# pcie-led.net
KiCad netlist of a schematic drawn in EAGLE
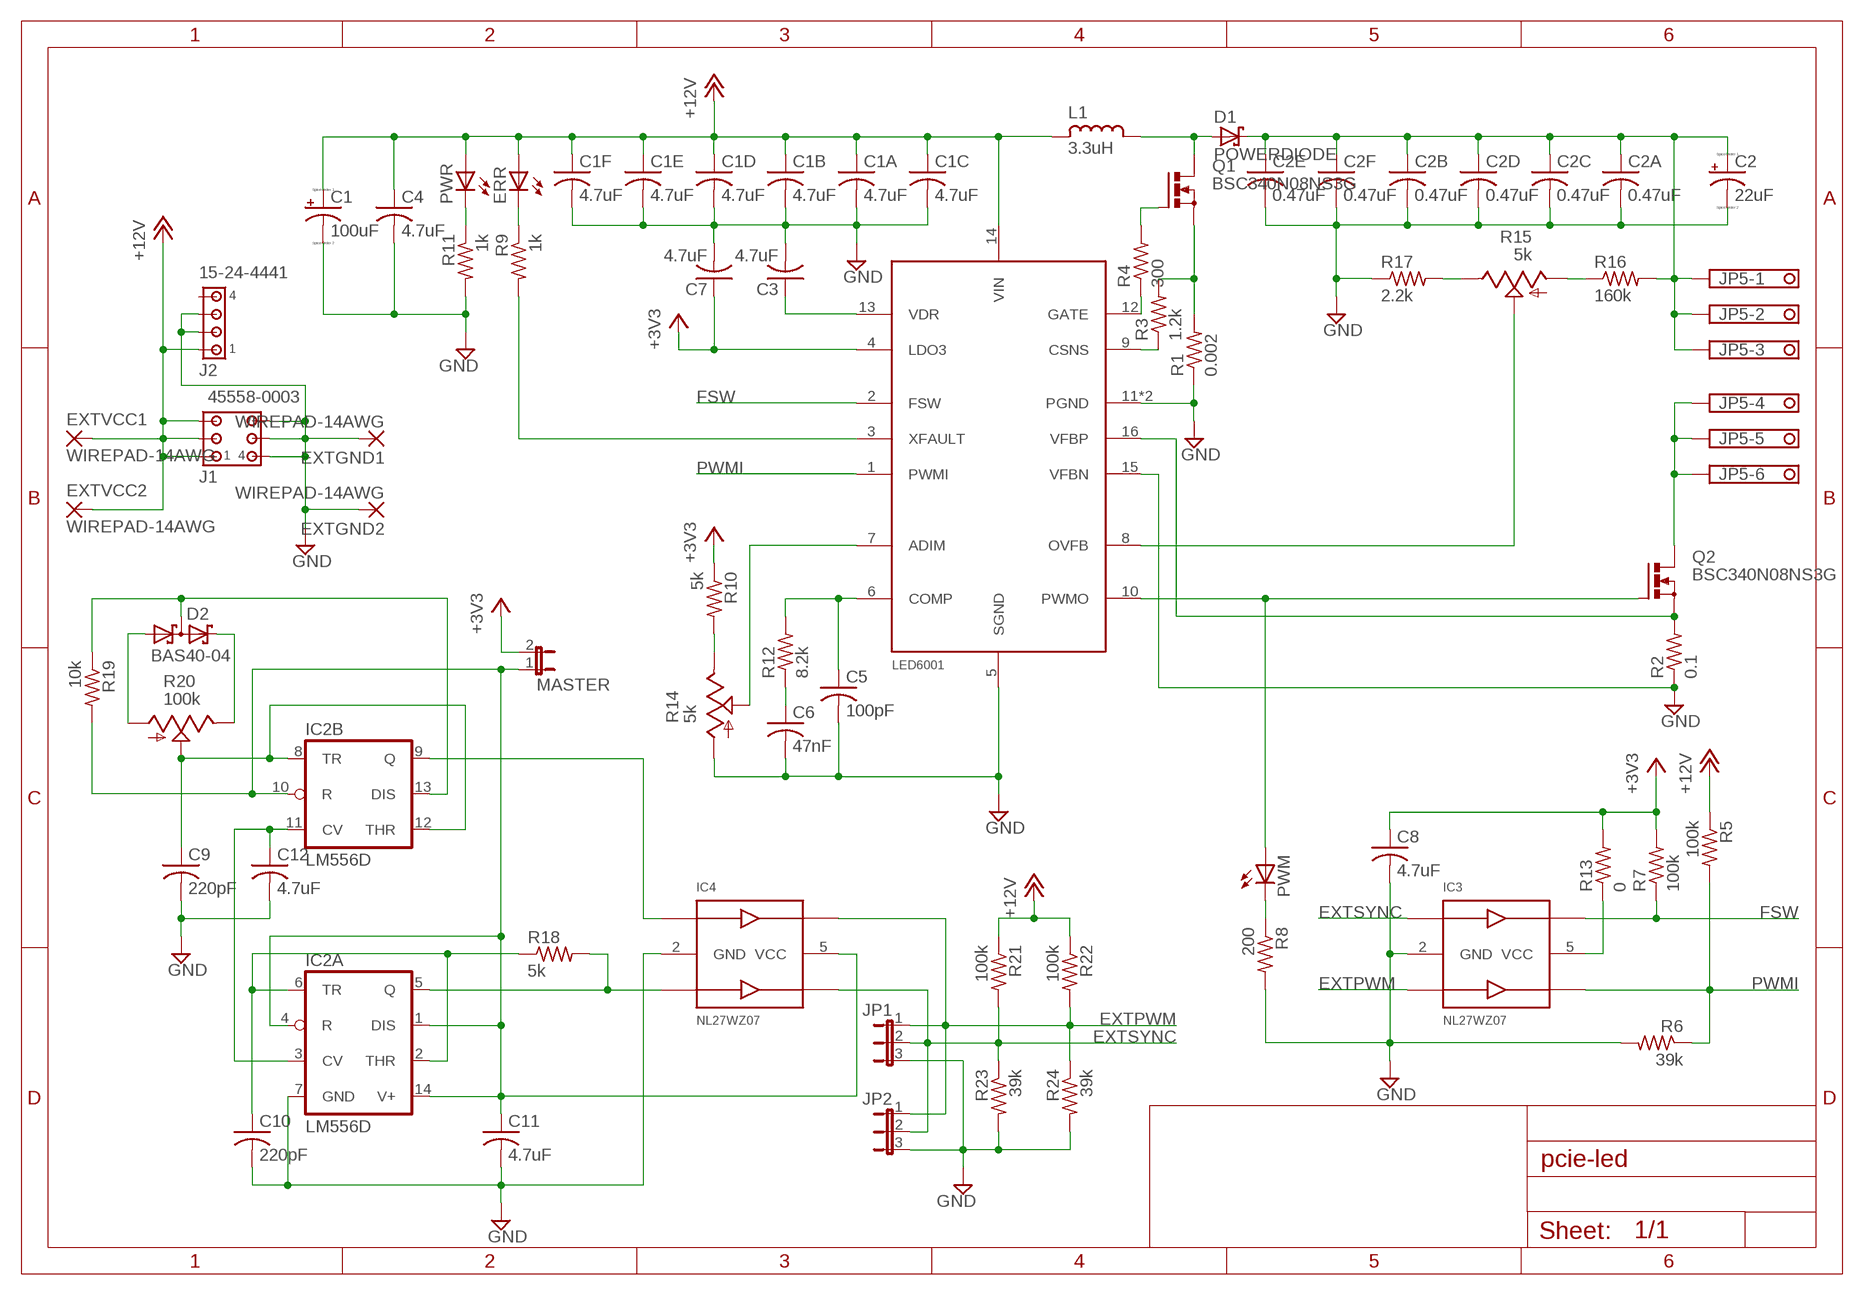
[diagram p0: schematic, sheet 1]

(export (version "E")
  (design (tool "Eeschema 10.0.6"))
  (components
    (comp (ref "C1")
      (value "100uF")
      (footprint "eagle-import:E3,5-8")
      (libsource (lib "eagle-import") (part "CPOL-USE3.5-8"))
    )
    (comp (ref "C1A")
      (value "4.7uF")
      (footprint "eagle-import:C0805")
      (libsource (lib "eagle-import") (part "C-USC0805"))
    )
    (comp (ref "C1B")
      (value "4.7uF")
      (footprint "eagle-import:C0805")
      (libsource (lib "eagle-import") (part "C-USC0805"))
    )
    (comp (ref "C1C")
      (value "4.7uF")
      (footprint "eagle-import:C0805")
      (libsource (lib "eagle-import") (part "C-USC0805"))
    )
    (comp (ref "C1D")
      (value "4.7uF")
      (footprint "eagle-import:C0805")
      (libsource (lib "eagle-import") (part "C-USC0805"))
    )
    (comp (ref "C1E")
      (value "4.7uF")
      (footprint "eagle-import:C0805")
      (libsource (lib "eagle-import") (part "C-USC0805"))
    )
    (comp (ref "C1F")
      (value "4.7uF")
      (footprint "eagle-import:C0805")
      (libsource (lib "eagle-import") (part "C-USC0805"))
    )
    (comp (ref "C2")
      (value "22uF")
      (footprint "eagle-import:E3,5-8")
      (libsource (lib "eagle-import") (part "CPOL-USE3.5-8"))
    )
    (comp (ref "C2A")
      (value "0.47uF")
      (footprint "eagle-import:C0805")
      (libsource (lib "eagle-import") (part "C-USC0805"))
    )
    (comp (ref "C2B")
      (value "0.47uF")
      (footprint "eagle-import:C0805")
      (libsource (lib "eagle-import") (part "C-USC0805"))
    )
    (comp (ref "C2C")
      (value "0.47uF")
      (footprint "eagle-import:C0805")
      (libsource (lib "eagle-import") (part "C-USC0805"))
    )
    (comp (ref "C2D")
      (value "0.47uF")
      (footprint "eagle-import:C0805")
      (libsource (lib "eagle-import") (part "C-USC0805"))
    )
    (comp (ref "C2E")
      (value "0.47uF")
      (footprint "eagle-import:C0805")
      (libsource (lib "eagle-import") (part "C-USC0805"))
    )
    (comp (ref "C2F")
      (value "0.47uF")
      (footprint "eagle-import:C0805")
      (libsource (lib "eagle-import") (part "C-USC0805"))
    )
    (comp (ref "C3")
      (value "4.7uF")
      (footprint "eagle-import:C0603")
      (libsource (lib "eagle-import") (part "C-USC0603"))
    )
    (comp (ref "C4")
      (value "4.7uF")
      (footprint "eagle-import:C0603")
      (libsource (lib "eagle-import") (part "C-USC0603"))
    )
    (comp (ref "C5")
      (value "100pF")
      (footprint "eagle-import:C0603")
      (libsource (lib "eagle-import") (part "C-USC0603"))
    )
    (comp (ref "C6")
      (value "47nF")
      (footprint "eagle-import:C0603")
      (libsource (lib "eagle-import") (part "C-USC0603"))
    )
    (comp (ref "C7")
      (value "4.7uF")
      (footprint "eagle-import:C0603")
      (libsource (lib "eagle-import") (part "C-USC0603"))
    )
    (comp (ref "C8")
      (value "4.7uF")
      (footprint "eagle-import:C0603")
      (libsource (lib "eagle-import") (part "C-USC0603"))
    )
    (comp (ref "C9")
      (value "220pF")
      (footprint "eagle-import:C0603")
      (libsource (lib "eagle-import") (part "C-USC0603"))
    )
    (comp (ref "C10")
      (value "220pF")
      (footprint "eagle-import:C0603")
      (libsource (lib "eagle-import") (part "C-USC0603"))
    )
    (comp (ref "C11")
      (value "4.7uF")
      (footprint "eagle-import:C0603")
      (libsource (lib "eagle-import") (part "C-USC0603"))
    )
    (comp (ref "C12")
      (value "4.7uF")
      (footprint "eagle-import:C0603")
      (libsource (lib "eagle-import") (part "C-USC0603"))
    )
    (comp (ref "D1")
      (value "POWERDIODE")
      (footprint "eagle-import:LFPACK56-TO277")
      (libsource (lib "eagle-import") (part "POWERDIODE"))
    )
    (comp (ref "D2")
      (value "BAS40-04")
      (footprint "eagle-import:SOT23")
      (libsource (lib "eagle-import") (part "BAS40-04"))
    )
    (comp (ref "ERR")
      (value "LEDCHIP-LED0805")
      (footprint "eagle-import:CHIP-LED0805")
      (libsource (lib "eagle-import") (part "LEDCHIP-LED0805"))
    )
    (comp (ref "EXTGND1")
      (value "WIREPAD-14AWG")
      (footprint "eagle-import:WIREPAD-14AWG")
      (libsource (lib "eagle-import") (part "WIREPAD-14AWG"))
    )
    (comp (ref "EXTGND2")
      (value "WIREPAD-14AWG")
      (footprint "eagle-import:WIREPAD-14AWG")
      (libsource (lib "eagle-import") (part "WIREPAD-14AWG"))
    )
    (comp (ref "EXTVCC1")
      (value "WIREPAD-14AWG")
      (footprint "eagle-import:WIREPAD-14AWG")
      (libsource (lib "eagle-import") (part "WIREPAD-14AWG"))
    )
    (comp (ref "EXTVCC2")
      (value "WIREPAD-14AWG")
      (footprint "eagle-import:WIREPAD-14AWG")
      (libsource (lib "eagle-import") (part "WIREPAD-14AWG"))
    )
    (comp (ref "IC1")
      (value "LED6001")
      (footprint "eagle-import:HTSSOP-16")
      (libsource (lib "eagle-import") (part "LED6001"))
    )
    (comp (ref "IC2")
      (value "LM556D")
      (footprint "eagle-import:SO14")
      (libsource (lib "eagle-import") (part "556DLM"))
    )
    (comp (ref "IC3")
      (value "NL27WZ07")
      (footprint "eagle-import:SOT363")
      (libsource (lib "eagle-import") (part "NL27WZ07"))
    )
    (comp (ref "IC4")
      (value "NL27WZ07")
      (footprint "eagle-import:SOT363")
      (libsource (lib "eagle-import") (part "NL27WZ07"))
    )
    (comp (ref "J1")
      (value "45558-0003")
      (footprint "eagle-import:45558-0003")
      (libsource (lib "eagle-import") (part "45558-0003"))
    )
    (comp (ref "J2")
      (value "15-24-4441")
      (footprint "eagle-import:15-24-4441")
      (libsource (lib "eagle-import") (part "15-24-4441"))
    )
    (comp (ref "JP1")
      (value "JP2E")
      (footprint "eagle-import:JP2")
      (libsource (lib "eagle-import") (part "JP2E"))
    )
    (comp (ref "JP2")
      (value "JP2E")
      (footprint "eagle-import:JP2")
      (libsource (lib "eagle-import") (part "JP2E"))
    )
    (comp (ref "JP5")
      (value "OSTTE06")
      (footprint "eagle-import:OSTTE06")
      (libsource (lib "eagle-import") (part "OSTTE06"))
    )
    (comp (ref "L1")
      (value "3.3uH")
      (footprint "eagle-import:SRP1770TA")
      (libsource (lib "eagle-import") (part "SRP1770TA"))
    )
    (comp (ref "MASTER")
      (value "JP1E")
      (footprint "eagle-import:JP1")
      (libsource (lib "eagle-import") (part "JP1E"))
    )
    (comp (ref "PWM")
      (value "LEDCHIP-LED0805")
      (footprint "eagle-import:CHIP-LED0805")
      (libsource (lib "eagle-import") (part "LEDCHIP-LED0805"))
    )
    (comp (ref "PWR")
      (value "LEDCHIP-LED0805")
      (footprint "eagle-import:CHIP-LED0805")
      (libsource (lib "eagle-import") (part "LEDCHIP-LED0805"))
    )
    (comp (ref "Q1")
      (value "BSC340N08NS3G")
      (footprint "eagle-import:PG-TDSON-8")
      (libsource (lib "eagle-import") (part "BSC340N08NS3G"))
    )
    (comp (ref "Q2")
      (value "BSC340N08NS3G")
      (footprint "eagle-import:PG-TDSON-8")
      (libsource (lib "eagle-import") (part "BSC340N08NS3G"))
    )
    (comp (ref "R1")
      (value "0.002")
      (footprint "eagle-import:R1206")
      (libsource (lib "eagle-import") (part "R-US_R1206"))
    )
    (comp (ref "R2")
      (value "0.1")
      (footprint "eagle-import:R2512")
      (libsource (lib "eagle-import") (part "R-US_R2512"))
    )
    (comp (ref "R3")
      (value "1.2k")
      (footprint "eagle-import:R0603")
      (libsource (lib "eagle-import") (part "R-US_R0603"))
    )
    (comp (ref "R4")
      (value "300")
      (footprint "eagle-import:R0603")
      (libsource (lib "eagle-import") (part "R-US_R0603"))
    )
    (comp (ref "R5")
      (value "100k")
      (footprint "eagle-import:R0603")
      (libsource (lib "eagle-import") (part "R-US_R0603"))
    )
    (comp (ref "R6")
      (value "39k")
      (footprint "eagle-import:R0603")
      (libsource (lib "eagle-import") (part "R-US_R0603"))
    )
    (comp (ref "R7")
      (value "100k")
      (footprint "eagle-import:R0603")
      (libsource (lib "eagle-import") (part "R-US_R0603"))
    )
    (comp (ref "R8")
      (value "200")
      (footprint "eagle-import:R0603")
      (libsource (lib "eagle-import") (part "R-US_R0603"))
    )
    (comp (ref "R9")
      (value "1k")
      (footprint "eagle-import:R0603")
      (libsource (lib "eagle-import") (part "R-US_R0603"))
    )
    (comp (ref "R10")
      (value "5k")
      (footprint "eagle-import:R0603")
      (libsource (lib "eagle-import") (part "R-US_R0603"))
    )
    (comp (ref "R11")
      (value "1k")
      (footprint "eagle-import:R0603")
      (libsource (lib "eagle-import") (part "R-US_R0603"))
    )
    (comp (ref "R12")
      (value "8.2k")
      (footprint "eagle-import:R0603")
      (libsource (lib "eagle-import") (part "R-US_R0603"))
    )
    (comp (ref "R13")
      (value "0")
      (footprint "eagle-import:R0603")
      (libsource (lib "eagle-import") (part "R-US_R0603"))
    )
    (comp (ref "R14")
      (value "5k")
      (footprint "eagle-import:ST-4EB")
      (libsource (lib "eagle-import") (part "ST4ETB"))
    )
    (comp (ref "R15")
      (value "5k")
      (footprint "eagle-import:ST-4EB")
      (libsource (lib "eagle-import") (part "ST4ETB"))
    )
    (comp (ref "R16")
      (value "160k")
      (footprint "eagle-import:R0603")
      (libsource (lib "eagle-import") (part "R-US_R0603"))
    )
    (comp (ref "R17")
      (value "2.2k")
      (footprint "eagle-import:R0603")
      (libsource (lib "eagle-import") (part "R-US_R0603"))
    )
    (comp (ref "R18")
      (value "5k")
      (footprint "eagle-import:R0603")
      (libsource (lib "eagle-import") (part "R-US_R0603"))
    )
    (comp (ref "R19")
      (value "10k")
      (footprint "eagle-import:R0603")
      (libsource (lib "eagle-import") (part "R-US_R0603"))
    )
    (comp (ref "R20")
      (value "100k")
      (footprint "eagle-import:P260T")
      (libsource (lib "eagle-import") (part "P260T"))
    )
    (comp (ref "R21")
      (value "100k")
      (footprint "eagle-import:R0603")
      (libsource (lib "eagle-import") (part "R-US_R0603"))
    )
    (comp (ref "R22")
      (value "100k")
      (footprint "eagle-import:R0603")
      (libsource (lib "eagle-import") (part "R-US_R0603"))
    )
    (comp (ref "R23")
      (value "39k")
      (footprint "eagle-import:R0603")
      (libsource (lib "eagle-import") (part "R-US_R0603"))
    )
    (comp (ref "R24")
      (value "39k")
      (footprint "eagle-import:R0603")
      (libsource (lib "eagle-import") (part "R-US_R0603"))
    )
  )
  (nets
    (net (code "1") (name "+3V3") (class "Default")
      (node (ref "C7") (pin "1") (pinfunction "1_1") (pintype "passive"))
      (node (ref "C8") (pin "1") (pinfunction "1_1") (pintype "passive"))
      (node (ref "IC1") (pin "4") (pinfunction "LDO3_4") (pintype "bidirectional"))
      (node (ref "MASTER") (pin "2") (pinfunction "2_2") (pintype "passive"))
      (node (ref "R10") (pin "1") (pinfunction "1_1") (pintype "passive"))
      (node (ref "R13") (pin "2") (pinfunction "2_2") (pintype "passive"))
      (node (ref "R7") (pin "2") (pinfunction "2_2") (pintype "passive"))
    )
    (net (code "2") (name "+12V") (class "Default")
      (node (ref "C1") (pin "+") (pinfunction "+_+") (pintype "passive"))
      (node (ref "C1A") (pin "1") (pinfunction "1_1") (pintype "passive"))
      (node (ref "C1B") (pin "1") (pinfunction "1_1") (pintype "passive"))
      (node (ref "C1C") (pin "1") (pinfunction "1_1") (pintype "passive"))
      (node (ref "C1D") (pin "1") (pinfunction "1_1") (pintype "passive"))
      (node (ref "C1E") (pin "1") (pinfunction "1_1") (pintype "passive"))
      (node (ref "C1F") (pin "1") (pinfunction "1_1") (pintype "passive"))
      (node (ref "C4") (pin "1") (pinfunction "1_1") (pintype "passive"))
      (node (ref "ERR") (pin "A") (pinfunction "A_A") (pintype "passive"))
      (node (ref "EXTVCC1") (pin "TP") (pinfunction "P_TP") (pintype "passive"))
      (node (ref "EXTVCC2") (pin "TP") (pinfunction "P_TP") (pintype "passive"))
      (node (ref "IC1") (pin "14") (pinfunction "VIN_14") (pintype "bidirectional"))
      (node (ref "J1") (pin "1") (pinfunction "1_1") (pintype "passive"))
      (node (ref "J1") (pin "2") (pinfunction "2_2") (pintype "passive"))
      (node (ref "J1") (pin "3") (pinfunction "3_3") (pintype "passive"))
      (node (ref "J2") (pin "1") (pinfunction "1_1") (pintype "passive"))
      (node (ref "L1") (pin "P$1") (pinfunction "1_P$1") (pintype "passive"))
      (node (ref "PWR") (pin "A") (pinfunction "A_A") (pintype "passive"))
      (node (ref "R21") (pin "1") (pinfunction "1_1") (pintype "passive"))
      (node (ref "R22") (pin "1") (pinfunction "1_1") (pintype "passive"))
      (node (ref "R5") (pin "1") (pinfunction "1_1") (pintype "passive"))
    )
    (net (code "3") (name "/EXTPWM") (class "Default")
      (node (ref "IC3") (pin "3") (pinfunction "IN2_3") (pintype "bidirectional"))
      (node (ref "IC4") (pin "6") (pinfunction "OUT1_6") (pintype "bidirectional"))
      (node (ref "JP1") (pin "1") (pinfunction "1_1") (pintype "passive"))
      (node (ref "JP2") (pin "1") (pinfunction "1_1") (pintype "passive"))
      (node (ref "R22") (pin "2") (pinfunction "2_2") (pintype "passive"))
      (node (ref "R24") (pin "1") (pinfunction "1_1") (pintype "passive"))
    )
    (net (code "4") (name "/EXTSYNC") (class "Default")
      (node (ref "IC3") (pin "1") (pinfunction "IN1_1") (pintype "bidirectional"))
      (node (ref "IC4") (pin "4") (pinfunction "OUT2_4") (pintype "bidirectional"))
      (node (ref "JP1") (pin "2") (pinfunction "2_2") (pintype "passive"))
      (node (ref "JP2") (pin "2") (pinfunction "2_2") (pintype "passive"))
      (node (ref "R21") (pin "2") (pinfunction "2_2") (pintype "passive"))
      (node (ref "R23") (pin "1") (pinfunction "1_1") (pintype "passive"))
    )
    (net (code "5") (name "/FSW") (class "Default")
      (node (ref "IC1") (pin "2") (pinfunction "FSW_2") (pintype "bidirectional"))
      (node (ref "IC3") (pin "6") (pinfunction "OUT1_6") (pintype "bidirectional"))
      (node (ref "R7") (pin "1") (pinfunction "1_1") (pintype "passive"))
    )
    (net (code "6") (name "/PWMI") (class "Default")
      (node (ref "IC1") (pin "1") (pinfunction "PWMI_1") (pintype "bidirectional"))
      (node (ref "IC3") (pin "4") (pinfunction "OUT2_4") (pintype "bidirectional"))
      (node (ref "R5") (pin "2") (pinfunction "2_2") (pintype "passive"))
      (node (ref "R6") (pin "1") (pinfunction "1_1") (pintype "passive"))
    )
    (net (code "7") (name "GND") (class "Default")
      (node (ref "C1") (pin "-") (pinfunction "-_-") (pintype "passive"))
      (node (ref "C10") (pin "2") (pinfunction "2_2") (pintype "passive"))
      (node (ref "C11") (pin "2") (pinfunction "2_2") (pintype "passive"))
      (node (ref "C12") (pin "2") (pinfunction "2_2") (pintype "passive"))
      (node (ref "C1A") (pin "2") (pinfunction "2_2") (pintype "passive"))
      (node (ref "C1B") (pin "2") (pinfunction "2_2") (pintype "passive"))
      (node (ref "C1C") (pin "2") (pinfunction "2_2") (pintype "passive"))
      (node (ref "C1D") (pin "2") (pinfunction "2_2") (pintype "passive"))
      (node (ref "C1E") (pin "2") (pinfunction "2_2") (pintype "passive"))
      (node (ref "C1F") (pin "2") (pinfunction "2_2") (pintype "passive"))
      (node (ref "C2") (pin "-") (pinfunction "-_-") (pintype "passive"))
      (node (ref "C2A") (pin "2") (pinfunction "2_2") (pintype "passive"))
      (node (ref "C2B") (pin "2") (pinfunction "2_2") (pintype "passive"))
      (node (ref "C2C") (pin "2") (pinfunction "2_2") (pintype "passive"))
      (node (ref "C2D") (pin "2") (pinfunction "2_2") (pintype "passive"))
      (node (ref "C2E") (pin "2") (pinfunction "2_2") (pintype "passive"))
      (node (ref "C2F") (pin "2") (pinfunction "2_2") (pintype "passive"))
      (node (ref "C3") (pin "2") (pinfunction "2_2") (pintype "passive"))
      (node (ref "C4") (pin "2") (pinfunction "2_2") (pintype "passive"))
      (node (ref "C5") (pin "2") (pinfunction "2_2") (pintype "passive"))
      (node (ref "C6") (pin "2") (pinfunction "2_2") (pintype "passive"))
      (node (ref "C7") (pin "2") (pinfunction "2_2") (pintype "passive"))
      (node (ref "C8") (pin "2") (pinfunction "2_2") (pintype "passive"))
      (node (ref "C9") (pin "2") (pinfunction "2_2") (pintype "passive"))
      (node (ref "EXTGND1") (pin "TP") (pinfunction "P_TP") (pintype "passive"))
      (node (ref "EXTGND2") (pin "TP") (pinfunction "P_TP") (pintype "passive"))
      (node (ref "IC1") (pin "11") (pinfunction "PGND_11") (pintype "bidirectional"))
      (node (ref "IC1") (pin "15") (pinfunction "VFBN_15") (pintype "bidirectional"))
      (node (ref "IC1") (pin "5") (pinfunction "SGND_5") (pintype "bidirectional"))
      (node (ref "IC1") (pin "PAD") (pinfunction "PGND_PAD") (pintype "bidirectional"))
      (node (ref "IC2") (pin "7") (pinfunction "GND_7") (pintype "power_in"))
      (node (ref "IC3") (pin "2") (pinfunction "GND_2") (pintype "bidirectional"))
      (node (ref "IC4") (pin "2") (pinfunction "GND_2") (pintype "bidirectional"))
      (node (ref "J1") (pin "4") (pinfunction "4_4") (pintype "passive"))
      (node (ref "J1") (pin "5") (pinfunction "5_5") (pintype "passive"))
      (node (ref "J1") (pin "6") (pinfunction "6_6") (pintype "passive"))
      (node (ref "J2") (pin "2") (pinfunction "2_2") (pintype "passive"))
      (node (ref "J2") (pin "3") (pinfunction "3_3") (pintype "passive"))
      (node (ref "JP1") (pin "3") (pinfunction "3_3") (pintype "passive"))
      (node (ref "JP2") (pin "3") (pinfunction "3_3") (pintype "passive"))
      (node (ref "R1") (pin "1") (pinfunction "1_1") (pintype "passive"))
      (node (ref "R11") (pin "2") (pinfunction "2_2") (pintype "passive"))
      (node (ref "R14") (pin "1") (pinfunction "A_1") (pintype "passive"))
      (node (ref "R17") (pin "1") (pinfunction "1_1") (pintype "passive"))
      (node (ref "R2") (pin "1") (pinfunction "1_1") (pintype "passive"))
      (node (ref "R23") (pin "2") (pinfunction "2_2") (pintype "passive"))
      (node (ref "R24") (pin "2") (pinfunction "2_2") (pintype "passive"))
      (node (ref "R6") (pin "2") (pinfunction "2_2") (pintype "passive"))
      (node (ref "R8") (pin "2") (pinfunction "2_2") (pintype "passive"))
    )
    (net (code "8") (name "Net-(C6-Pad1)") (class "Default")
      (node (ref "C6") (pin "1") (pinfunction "1_1") (pintype "passive"))
      (node (ref "R12") (pin "1") (pinfunction "1_1") (pintype "passive"))
    )
    (net (code "9") (name "Net-(D2-A1)") (class "Default")
      (node (ref "D2") (pin "1") (pinfunction "A1_1") (pintype "passive"))
      (node (ref "R20") (pin "1") (pinfunction "A_1") (pintype "passive"))
    )
    (net (code "10") (name "Net-(D2-C1A2)") (class "Default")
      (node (ref "D2") (pin "3") (pinfunction "C1A2_3") (pintype "passive"))
      (node (ref "IC2") (pin "13") (pinfunction "DIS_13") (pintype "input"))
      (node (ref "R19") (pin "1") (pinfunction "1_1") (pintype "passive"))
    )
    (net (code "11") (name "Net-(D2-C2)") (class "Default")
      (node (ref "D2") (pin "2") (pinfunction "C2_2") (pintype "passive"))
      (node (ref "R20") (pin "3") (pinfunction "E_3") (pintype "passive"))
    )
    (net (code "12") (name "Net-(ERR-PadC)") (class "Default")
      (node (ref "ERR") (pin "C") (pinfunction "C_C") (pintype "passive"))
      (node (ref "R9") (pin "1") (pinfunction "1_1") (pintype "passive"))
    )
    (net (code "13") (name "Net-(IC1-ADIM)") (class "Default")
      (node (ref "IC1") (pin "7") (pinfunction "ADIM_7") (pintype "bidirectional"))
      (node (ref "R14") (pin "2") (pinfunction "S_2") (pintype "passive"))
    )
    (net (code "14") (name "Net-(IC1-COMP)") (class "Default")
      (node (ref "C5") (pin "1") (pinfunction "1_1") (pintype "passive"))
      (node (ref "IC1") (pin "6") (pinfunction "COMP_6") (pintype "bidirectional"))
      (node (ref "R12") (pin "2") (pinfunction "2_2") (pintype "passive"))
    )
    (net (code "15") (name "Net-(IC1-CSNS)") (class "Default")
      (node (ref "IC1") (pin "9") (pinfunction "CSNS_9") (pintype "bidirectional"))
      (node (ref "R3") (pin "1") (pinfunction "1_1") (pintype "passive"))
    )
    (net (code "16") (name "Net-(IC1-GATE)") (class "Default")
      (node (ref "IC1") (pin "12") (pinfunction "GATE_12") (pintype "bidirectional"))
      (node (ref "R4") (pin "1") (pinfunction "1_1") (pintype "passive"))
    )
    (net (code "17") (name "Net-(IC1-OVFB)") (class "Default")
      (node (ref "IC1") (pin "8") (pinfunction "OVFB_8") (pintype "bidirectional"))
      (node (ref "R15") (pin "2") (pinfunction "S_2") (pintype "passive"))
    )
    (net (code "18") (name "Net-(IC1-PWMO)") (class "Default")
      (node (ref "IC1") (pin "10") (pinfunction "PWMO_10") (pintype "bidirectional"))
      (node (ref "PWM") (pin "A") (pinfunction "A_A") (pintype "passive"))
      (node (ref "Q2") (pin "4") (pinfunction "G_4") (pintype "passive"))
    )
    (net (code "19") (name "Net-(IC1-VDR)") (class "Default")
      (node (ref "C3") (pin "1") (pinfunction "1_1") (pintype "passive"))
      (node (ref "IC1") (pin "13") (pinfunction "VDR_13") (pintype "bidirectional"))
    )
    (net (code "20") (name "Net-(IC1-VFBP)") (class "Default")
      (node (ref "IC1") (pin "16") (pinfunction "VFBP_16") (pintype "bidirectional"))
      (node (ref "Q2") (pin "1") (pinfunction "S_1") (pintype "passive"))
      (node (ref "Q2") (pin "2") (pinfunction "S_2") (pintype "passive"))
      (node (ref "Q2") (pin "3") (pinfunction "S_3") (pintype "passive"))
      (node (ref "R2") (pin "2") (pinfunction "2_2") (pintype "passive"))
    )
    (net (code "21") (name "Net-(IC1-XFAULT)") (class "Default")
      (node (ref "IC1") (pin "3") (pinfunction "XFAULT_3") (pintype "bidirectional"))
      (node (ref "R9") (pin "2") (pinfunction "2_2") (pintype "passive"))
    )
    (net (code "22") (name "Net-(IC2A-CV)") (class "Default")
      (node (ref "C12") (pin "1") (pinfunction "1_1") (pintype "passive"))
      (node (ref "IC2") (pin "11") (pinfunction "CV_11") (pintype "input"))
      (node (ref "IC2") (pin "3") (pinfunction "CV_3") (pintype "input"))
    )
    (net (code "23") (name "Net-(IC2A-DIS)") (class "Default")
      (node (ref "C11") (pin "1") (pinfunction "1_1") (pintype "passive"))
      (node (ref "IC2") (pin "1") (pinfunction "DIS_1") (pintype "input"))
      (node (ref "IC2") (pin "10") (pinfunction "R_10") (pintype "input"))
      (node (ref "IC2") (pin "14") (pinfunction "V+_14") (pintype "power_in"))
      (node (ref "IC2") (pin "4") (pinfunction "R_4") (pintype "input"))
      (node (ref "IC4") (pin "5") (pinfunction "VCC_5") (pintype "bidirectional"))
      (node (ref "MASTER") (pin "1") (pinfunction "1_1") (pintype "passive"))
      (node (ref "R19") (pin "2") (pinfunction "2_2") (pintype "passive"))
    )
    (net (code "24") (name "Net-(IC2A-Q)") (class "Default")
      (node (ref "IC2") (pin "5") (pinfunction "Q_5") (pintype "output"))
      (node (ref "IC4") (pin "3") (pinfunction "IN2_3") (pintype "bidirectional"))
      (node (ref "R18") (pin "2") (pinfunction "2_2") (pintype "passive"))
    )
    (net (code "25") (name "Net-(IC2A-THR)") (class "Default")
      (node (ref "C10") (pin "1") (pinfunction "1_1") (pintype "passive"))
      (node (ref "IC2") (pin "2") (pinfunction "THR_2") (pintype "input"))
      (node (ref "IC2") (pin "6") (pinfunction "TR_6") (pintype "input"))
      (node (ref "R18") (pin "1") (pinfunction "1_1") (pintype "passive"))
    )
    (net (code "26") (name "Net-(IC2B-Q)") (class "Default")
      (node (ref "IC2") (pin "9") (pinfunction "Q_9") (pintype "output"))
      (node (ref "IC4") (pin "1") (pinfunction "IN1_1") (pintype "bidirectional"))
    )
    (net (code "27") (name "Net-(IC2B-THR)") (class "Default")
      (node (ref "C9") (pin "1") (pinfunction "1_1") (pintype "passive"))
      (node (ref "IC2") (pin "12") (pinfunction "THR_12") (pintype "input"))
      (node (ref "IC2") (pin "8") (pinfunction "TR_8") (pintype "input"))
      (node (ref "R20") (pin "2") (pinfunction "S_2") (pintype "passive"))
    )
    (net (code "28") (name "Net-(IC3-VCC)") (class "Default")
      (node (ref "IC3") (pin "5") (pinfunction "VCC_5") (pintype "bidirectional"))
      (node (ref "R13") (pin "1") (pinfunction "1_1") (pintype "passive"))
    )
    (net (code "29") (name "Net-(JP5A-K)") (class "Default")
      (node (ref "C2") (pin "+") (pinfunction "+_+") (pintype "passive"))
      (node (ref "C2A") (pin "1") (pinfunction "1_1") (pintype "passive"))
      (node (ref "C2B") (pin "1") (pinfunction "1_1") (pintype "passive"))
      (node (ref "C2C") (pin "1") (pinfunction "1_1") (pintype "passive"))
      (node (ref "C2D") (pin "1") (pinfunction "1_1") (pintype "passive"))
      (node (ref "C2E") (pin "1") (pinfunction "1_1") (pintype "passive"))
      (node (ref "C2F") (pin "1") (pinfunction "1_1") (pintype "passive"))
      (node (ref "D1") (pin "C1") (pinfunction "C_C1") (pintype "passive"))
      (node (ref "D1") (pin "C2") (pinfunction "C_C2") (pintype "passive"))
      (node (ref "D1") (pin "C3") (pinfunction "C_C3") (pintype "passive"))
      (node (ref "D1") (pin "C4") (pinfunction "C_C4") (pintype "passive"))
      (node (ref "D1") (pin "TH") (pinfunction "C_TH") (pintype "passive"))
      (node (ref "JP5") (pin "1") (pinfunction "K_1") (pintype "passive"))
      (node (ref "JP5") (pin "2") (pinfunction "K_2") (pintype "passive"))
      (node (ref "JP5") (pin "3") (pinfunction "K_3") (pintype "passive"))
      (node (ref "R16") (pin "2") (pinfunction "2_2") (pintype "passive"))
    )
    (net (code "30") (name "Net-(JP5D-K)") (class "Default")
      (node (ref "JP5") (pin "4") (pinfunction "K_4") (pintype "passive"))
      (node (ref "JP5") (pin "5") (pinfunction "K_5") (pintype "passive"))
      (node (ref "JP5") (pin "6") (pinfunction "K_6") (pintype "passive"))
      (node (ref "Q2") (pin "5") (pinfunction "D_5") (pintype "passive"))
      (node (ref "Q2") (pin "6") (pinfunction "D_6") (pintype "passive"))
      (node (ref "Q2") (pin "7") (pinfunction "D_7") (pintype "passive"))
      (node (ref "Q2") (pin "8") (pinfunction "D_8") (pintype "passive"))
      (node (ref "Q2") (pin "TH") (pinfunction "D_TH") (pintype "passive"))
    )
    (net (code "31") (name "Net-(L1-4)") (class "Default")
      (node (ref "D1") (pin "A") (pinfunction "A_A") (pintype "passive"))
      (node (ref "L1") (pin "P$2") (pinfunction "4_P$2") (pintype "passive"))
      (node (ref "Q1") (pin "5") (pinfunction "D_5") (pintype "passive"))
      (node (ref "Q1") (pin "6") (pinfunction "D_6") (pintype "passive"))
      (node (ref "Q1") (pin "7") (pinfunction "D_7") (pintype "passive"))
      (node (ref "Q1") (pin "8") (pinfunction "D_8") (pintype "passive"))
      (node (ref "Q1") (pin "TH") (pinfunction "D_TH") (pintype "passive"))
    )
    (net (code "32") (name "Net-(PWM-PadC)") (class "Default")
      (node (ref "PWM") (pin "C") (pinfunction "C_C") (pintype "passive"))
      (node (ref "R8") (pin "1") (pinfunction "1_1") (pintype "passive"))
    )
    (net (code "33") (name "Net-(PWR-PadC)") (class "Default")
      (node (ref "PWR") (pin "C") (pinfunction "C_C") (pintype "passive"))
      (node (ref "R11") (pin "1") (pinfunction "1_1") (pintype "passive"))
    )
    (net (code "34") (name "Net-(Q1-G)") (class "Default")
      (node (ref "Q1") (pin "4") (pinfunction "G_4") (pintype "passive"))
      (node (ref "R4") (pin "2") (pinfunction "2_2") (pintype "passive"))
    )
    (net (code "35") (name "Net-(Q1-S-Pad1)") (class "Default")
      (node (ref "Q1") (pin "1") (pinfunction "S_1") (pintype "passive"))
      (node (ref "Q1") (pin "2") (pinfunction "S_2") (pintype "passive"))
      (node (ref "Q1") (pin "3") (pinfunction "S_3") (pintype "passive"))
      (node (ref "R1") (pin "2") (pinfunction "2_2") (pintype "passive"))
      (node (ref "R3") (pin "2") (pinfunction "2_2") (pintype "passive"))
    )
    (net (code "36") (name "Net-(R14-E)") (class "Default")
      (node (ref "R10") (pin "2") (pinfunction "2_2") (pintype "passive"))
      (node (ref "R14") (pin "3") (pinfunction "E_3") (pintype "passive"))
    )
    (net (code "37") (name "Net-(R15-A)") (class "Default")
      (node (ref "R15") (pin "1") (pinfunction "A_1") (pintype "passive"))
      (node (ref "R16") (pin "1") (pinfunction "1_1") (pintype "passive"))
    )
    (net (code "38") (name "Net-(R15-E)") (class "Default")
      (node (ref "R15") (pin "3") (pinfunction "E_3") (pintype "passive"))
      (node (ref "R17") (pin "2") (pinfunction "2_2") (pintype "passive"))
    )
    (net (code "39") (name "unconnected-(J2-Pad4)") (class "Default")
      (node (ref "J2") (pin "4") (pinfunction "4_4") (pintype "passive"))
    )
  )
)
